# temp_sensor.net
KiCad netlist of a schematic drawn in EAGLE
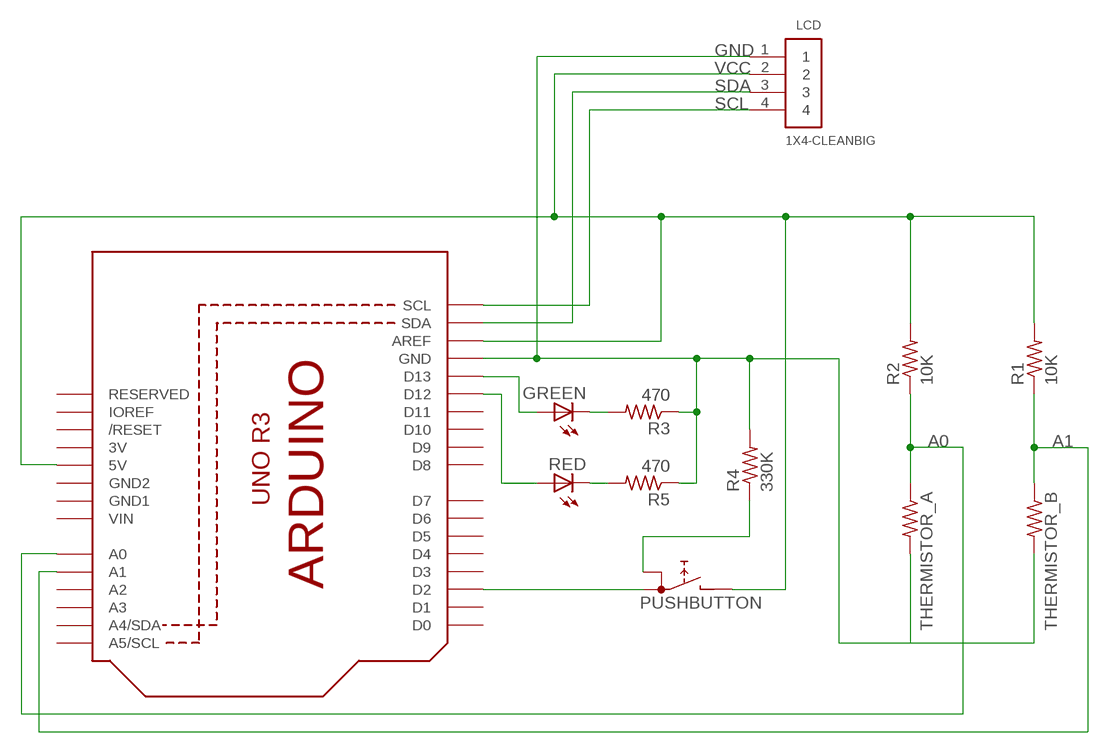
[diagram p0: schematic, sheet 1]

(export (version "E")
  (design (tool "Eeschema 10.0.6"))
  (components
    (comp (ref "GREEN")
      (value "LED3MM")
      (footprint "eagle-import:LED3MM")
      (libsource (lib "eagle-import") (part "LED3MM"))
    )
    (comp (ref "LCD")
      (value "1X4-CLEANBIG")
      (footprint "eagle-import:1X04-CLEANBIG")
      (libsource (lib "eagle-import") (part "1X4-CLEANBIG"))
    )
    (comp (ref "PUSHBUTTON")
      (value "RDT1034")
      (footprint "eagle-import:RDT1034")
      (libsource (lib "eagle-import") (part "RDT1034"))
    )
    (comp (ref "R1")
      (value "10K")
      (footprint "eagle-import:0204_7")
      (libsource (lib "eagle-import") (part "R-US_0204/7"))
    )
    (comp (ref "R2")
      (value "10K")
      (footprint "eagle-import:0204_7")
      (libsource (lib "eagle-import") (part "R-US_0204/7"))
    )
    (comp (ref "R3")
      (value "470")
      (footprint "eagle-import:0204_7")
      (libsource (lib "eagle-import") (part "R-US_0204/7"))
    )
    (comp (ref "R4")
      (value "330K")
      (footprint "eagle-import:0204_7")
      (libsource (lib "eagle-import") (part "R-US_0204/7"))
    )
    (comp (ref "R5")
      (value "470")
      (footprint "eagle-import:0204_7")
      (libsource (lib "eagle-import") (part "R-US_0204/7"))
    )
    (comp (ref "RED")
      (value "LED3MM")
      (footprint "eagle-import:LED3MM")
      (libsource (lib "eagle-import") (part "LED3MM"))
    )
    (comp (ref "THERMISTOR_A")
      (value "R-US_0204/7")
      (footprint "eagle-import:0204_7")
      (libsource (lib "eagle-import") (part "R-US_0204/7"))
    )
    (comp (ref "THERMISTOR_B")
      (value "R-US_0204/7")
      (footprint "eagle-import:0204_7")
      (libsource (lib "eagle-import") (part "R-US_0204/7"))
    )
    (comp (ref "U1")
      (value "ARDUINOR3-DIMENSION")
      (footprint "eagle-import:ARDUINOR3")
      (libsource (lib "eagle-import") (part "ARDUINOR3-DIMENSION"))
    )
  )
  (nets
    (net (code "1") (name "/3V") (class "Default")
      (node (ref "U1") (pin "3V") (pinfunction "3V_3V") (pintype "power_in"))
    )
    (net (code "2") (name "/A0") (class "Default")
      (node (ref "R2") (pin "1") (pinfunction "1_1") (pintype "passive"))
      (node (ref "THERMISTOR_A") (pin "1") (pinfunction "1_1") (pintype "passive"))
      (node (ref "U1") (pin "A0") (pinfunction "A0_A0") (pintype "bidirectional"))
    )
    (net (code "3") (name "/A1") (class "Default")
      (node (ref "R1") (pin "1") (pinfunction "1_1") (pintype "passive"))
      (node (ref "THERMISTOR_B") (pin "1") (pinfunction "1_1") (pintype "passive"))
      (node (ref "U1") (pin "A1") (pinfunction "A1_A1") (pintype "bidirectional"))
    )
    (net (code "4") (name "/GND") (class "Default")
      (node (ref "LCD") (pin "1") (pinfunction "1_1") (pintype "bidirectional"))
      (node (ref "R3") (pin "1") (pinfunction "1_1") (pintype "passive"))
      (node (ref "R4") (pin "2") (pinfunction "2_2") (pintype "passive"))
      (node (ref "R5") (pin "1") (pinfunction "1_1") (pintype "passive"))
      (node (ref "THERMISTOR_A") (pin "2") (pinfunction "2_2") (pintype "passive"))
      (node (ref "THERMISTOR_B") (pin "2") (pinfunction "2_2") (pintype "passive"))
      (node (ref "U1") (pin "GND") (pinfunction "GND_GND") (pintype "power_in"))
    )
    (net (code "5") (name "/GND1") (class "Default")
      (node (ref "U1") (pin "GND1") (pinfunction "GND1_GND1") (pintype "power_in"))
    )
    (net (code "6") (name "/GND2") (class "Default")
      (node (ref "U1") (pin "GND2") (pinfunction "GND2_GND2") (pintype "power_in"))
    )
    (net (code "7") (name "/SCL") (class "Default")
      (node (ref "LCD") (pin "4") (pinfunction "4_4") (pintype "bidirectional"))
      (node (ref "U1") (pin "SCL") (pinfunction "SCL_SCL") (pintype "bidirectional"))
    )
    (net (code "8") (name "/SDA") (class "Default")
      (node (ref "LCD") (pin "3") (pinfunction "3_3") (pintype "bidirectional"))
      (node (ref "U1") (pin "SDA") (pinfunction "SDA_SDA") (pintype "bidirectional"))
    )
    (net (code "9") (name "/VCC") (class "Default")
      (node (ref "LCD") (pin "2") (pinfunction "2_2") (pintype "bidirectional"))
      (node (ref "PUSHBUTTON") (pin "B") (pinfunction "B_B") (pintype "passive"))
      (node (ref "R1") (pin "2") (pinfunction "2_2") (pintype "passive"))
      (node (ref "R2") (pin "2") (pinfunction "2_2") (pintype "passive"))
      (node (ref "U1") (pin "5V") (pinfunction "5V_5V") (pintype "power_in"))
      (node (ref "U1") (pin "AREF") (pinfunction "AREF_AREF") (pintype "bidirectional"))
    )
    (net (code "10") (name "/VIN") (class "Default")
      (node (ref "U1") (pin "VIN") (pinfunction "VIN_VIN") (pintype "power_in"))
    )
    (net (code "11") (name "Net-(GREEN-C)") (class "Default")
      (node (ref "GREEN") (pin "K") (pinfunction "C_K") (pintype "passive"))
      (node (ref "R3") (pin "2") (pinfunction "2_2") (pintype "passive"))
    )
    (net (code "12") (name "Net-(GREEN-PadA)") (class "Default")
      (node (ref "GREEN") (pin "A") (pinfunction "A_A") (pintype "passive"))
      (node (ref "U1") (pin "D13") (pinfunction "D13_D13") (pintype "bidirectional"))
    )
    (net (code "13") (name "Net-(PUSHBUTTON-PadA)") (class "Default")
      (node (ref "PUSHBUTTON") (pin "A") (pinfunction "A_A") (pintype "passive"))
      (node (ref "R4") (pin "1") (pinfunction "1_1") (pintype "passive"))
    )
    (net (code "14") (name "Net-(PUSHBUTTON-PadA1)") (class "Default")
      (node (ref "PUSHBUTTON") (pin "A1") (pinfunction "A1_A1") (pintype "passive"))
      (node (ref "U1") (pin "D2") (pinfunction "D2_D2") (pintype "bidirectional"))
    )
    (net (code "15") (name "Net-(RED-C)") (class "Default")
      (node (ref "R5") (pin "2") (pinfunction "2_2") (pintype "passive"))
      (node (ref "RED") (pin "K") (pinfunction "C_K") (pintype "passive"))
    )
    (net (code "16") (name "Net-(RED-PadA)") (class "Default")
      (node (ref "RED") (pin "A") (pinfunction "A_A") (pintype "passive"))
      (node (ref "U1") (pin "D12") (pinfunction "D12_D12") (pintype "bidirectional"))
    )
    (net (code "17") (name "unconnected-(U1-A4{slash}SDA-PadA4)") (class "Default")
      (node (ref "U1") (pin "A4") (pinfunction "A4/SDA_A4") (pintype "bidirectional"))
    )
    (net (code "18") (name "unconnected-(U1-A5{slash}SCL-PadA5)") (class "Default")
      (node (ref "U1") (pin "A5") (pinfunction "A5/SCL_A5") (pintype "bidirectional"))
    )
    (net (code "19") (name "unconnected-(U1-PadA2)") (class "Default")
      (node (ref "U1") (pin "A2") (pinfunction "A2_A2") (pintype "bidirectional"))
    )
    (net (code "20") (name "unconnected-(U1-PadA3)") (class "Default")
      (node (ref "U1") (pin "A3") (pinfunction "A3_A3") (pintype "bidirectional"))
    )
    (net (code "21") (name "unconnected-(U1-PadD0)") (class "Default")
      (node (ref "U1") (pin "D0") (pinfunction "D0_D0") (pintype "bidirectional"))
    )
    (net (code "22") (name "unconnected-(U1-PadD1)") (class "Default")
      (node (ref "U1") (pin "D1") (pinfunction "D1_D1") (pintype "bidirectional"))
    )
    (net (code "23") (name "unconnected-(U1-PadD3)") (class "Default")
      (node (ref "U1") (pin "D3") (pinfunction "D3_D3") (pintype "bidirectional"))
    )
    (net (code "24") (name "unconnected-(U1-PadD4)") (class "Default")
      (node (ref "U1") (pin "D4") (pinfunction "D4_D4") (pintype "bidirectional"))
    )
    (net (code "25") (name "unconnected-(U1-PadD5)") (class "Default")
      (node (ref "U1") (pin "D5") (pinfunction "D5_D5") (pintype "bidirectional"))
    )
    (net (code "26") (name "unconnected-(U1-PadD6)") (class "Default")
      (node (ref "U1") (pin "D6") (pinfunction "D6_D6") (pintype "bidirectional"))
    )
    (net (code "27") (name "unconnected-(U1-PadD7)") (class "Default")
      (node (ref "U1") (pin "D7") (pinfunction "D7_D7") (pintype "bidirectional"))
    )
    (net (code "28") (name "unconnected-(U1-PadD8)") (class "Default")
      (node (ref "U1") (pin "D8") (pinfunction "D8_D8") (pintype "bidirectional"))
    )
    (net (code "29") (name "unconnected-(U1-PadD9)") (class "Default")
      (node (ref "U1") (pin "D9") (pinfunction "D9_D9") (pintype "bidirectional"))
    )
    (net (code "30") (name "unconnected-(U1-PadD10)") (class "Default")
      (node (ref "U1") (pin "D10") (pinfunction "D10_D10") (pintype "bidirectional"))
    )
    (net (code "31") (name "unconnected-(U1-PadD11)") (class "Default")
      (node (ref "U1") (pin "D11") (pinfunction "D11_D11") (pintype "bidirectional"))
    )
    (net (code "32") (name "unconnected-(U1-PadIOREF)") (class "Default")
      (node (ref "U1") (pin "IOREF") (pinfunction "IOREF_IOREF") (pintype "output"))
    )
    (net (code "33") (name "unconnected-(U1-PadRESERVED)") (class "Default")
      (node (ref "U1") (pin "RESERVED") (pinfunction "RESERVED_RESERVED") (pintype "no_connect"))
    )
    (net (code "34") (name "unconnected-(U1-{slash}RESET-PadRESET)") (class "Default")
      (node (ref "U1") (pin "RESET") (pinfunction "/RESET_RESET") (pintype "bidirectional"))
    )
  )
)
